# CPU_superviser.net
KiCad netlist of a schematic drawn in Altium Designer
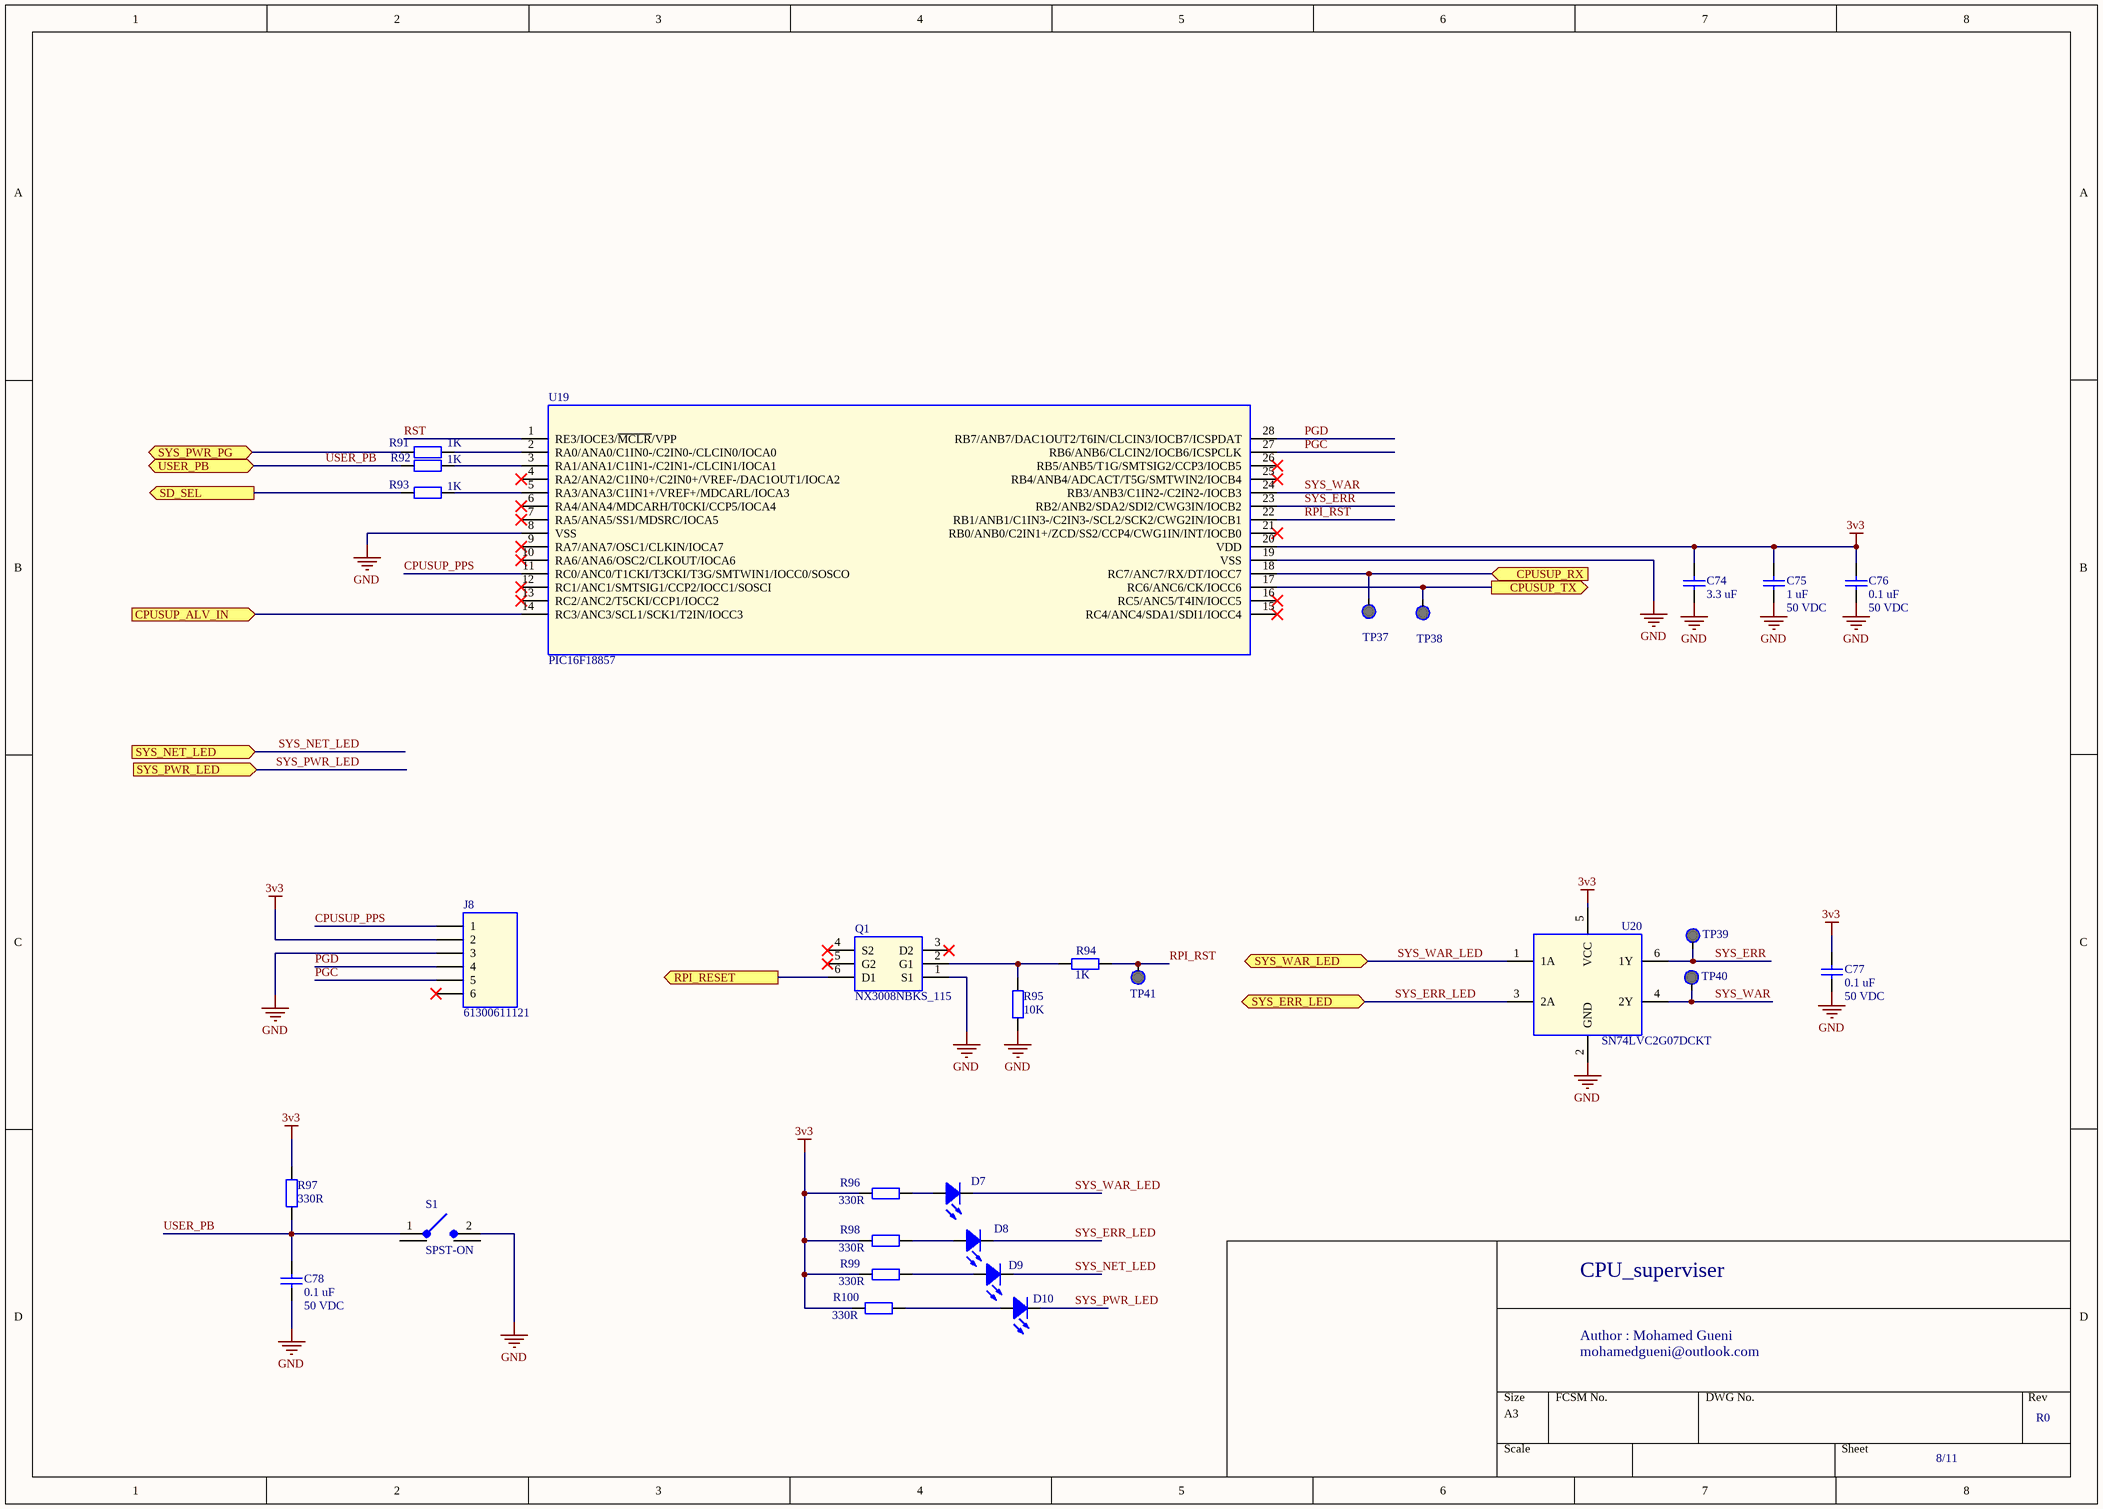
[diagram p0: CPU_superviser.SchDoc]

(export (version "E")
  (design (tool "Eeschema 10.0.6"))
  (components
    (comp (ref "C74")
      (value "Capacitor")
      (footprint "CAPC1608N")
      (fields (field (name "PART NUMBER") "CAP-000000008") (field (name "VALUE 1") "3.3 uF"))
      (libsource (lib "DB") (part "Capacitor"))
    )
    (comp (ref "C75")
      (value "Capacitor")
      (footprint "CAPC1608N")
      (fields
        (field (name "PART NUMBER") "CAP-000000005")
        (field (name "VALUE 1") "1 uF")
        (field (name "VALUE 2") "50 VDC")
      )
      (libsource (lib "DB") (part "Capacitor"))
    )
    (comp (ref "C76")
      (value "Capacitor")
      (footprint "CAPC1608N")
      (fields
        (field (name "PART NUMBER") "CAP-000000003")
        (field (name "VALUE 1") "0.1 uF")
        (field (name "VALUE 2") "50 VDC")
      )
      (libsource (lib "DB") (part "Capacitor"))
    )
    (comp (ref "C77")
      (value "Capacitor")
      (footprint "CAPC1608N")
      (fields
        (field (name "PART NUMBER") "CAP-000000003")
        (field (name "VALUE 1") "0.1 uF")
        (field (name "VALUE 2") "50 VDC")
      )
      (libsource (lib "DB") (part "Capacitor"))
    )
    (comp (ref "C78")
      (value "Capacitor")
      (footprint "CAPC1608N")
      (fields
        (field (name "PART NUMBER") "CAP-000000003")
        (field (name "VALUE 1") "0.1 uF")
        (field (name "VALUE 2") "50 VDC")
      )
      (libsource (lib "DB") (part "Capacitor"))
    )
    (comp (ref "D7")
      (value "150060BS75000")
      (footprint "LED0603")
      (fields (field (name "PART NUMBER") "LED-000000003"))
      (libsource (lib "DB") (part "LED"))
    )
    (comp (ref "D8")
      (value "150060RS75000")
      (footprint "LED0603")
      (fields (field (name "PART NUMBER") "LED-000000001"))
      (libsource (lib "DB") (part "LED"))
    )
    (comp (ref "D9")
      (value "150060GS75000")
      (footprint "LED0603")
      (fields (field (name "PART NUMBER") "LED-000000002"))
      (libsource (lib "DB") (part "LED"))
    )
    (comp (ref "D10")
      (value "150060GS75000")
      (footprint "LED0603")
      (fields (field (name "PART NUMBER") "LED-000000002"))
      (libsource (lib "DB") (part "LED"))
    )
    (comp (ref "J8")
      (value "61300611121")
      (footprint "HDRV6W64P0X254")
      (fields (field (name "PART NUMBER") "CON-000000010"))
      (libsource (lib "DB") (part "61300611121"))
    )
    (comp (ref "Q1")
      (value "NX3008NBKS_115")
      (footprint "SOT65P210X110-6N")
      (fields (field (name "PART NUMBER") "TRM-000000002"))
      (libsource (lib "DB") (part "NX3008NBKS_115"))
    )
    (comp (ref "R91")
      (value "Resistor")
      (footprint "RESC1608N")
      (fields (field (name "PART NUMBER") "RES-000000001") (field (name "VALUE 1") "1K"))
      (libsource (lib "DB") (part "Resistor"))
    )
    (comp (ref "R92")
      (value "Resistor")
      (footprint "RESC1608N")
      (fields (field (name "PART NUMBER") "RES-000000001") (field (name "VALUE 1") "1K"))
      (libsource (lib "DB") (part "Resistor"))
    )
    (comp (ref "R93")
      (value "Resistor")
      (footprint "RESC1608N")
      (fields (field (name "PART NUMBER") "RES-000000001") (field (name "VALUE 1") "1K"))
      (libsource (lib "DB") (part "Resistor"))
    )
    (comp (ref "R94")
      (value "Resistor")
      (footprint "RESC1608N")
      (fields (field (name "PART NUMBER") "RES-000000001") (field (name "VALUE 1") "1K"))
      (libsource (lib "DB") (part "Resistor"))
    )
    (comp (ref "R95")
      (value "Resistor")
      (footprint "RESC1608N")
      (fields (field (name "PART NUMBER") "RES-000000007") (field (name "VALUE 1") "10K"))
      (libsource (lib "") (part "Resistor_1"))
    )
    (comp (ref "R96")
      (value "Resistor")
      (footprint "RESC1608N")
      (fields (field (name "PART NUMBER") "RES-000000008") (field (name "VALUE 1") "330R"))
      (libsource (lib "DB") (part "Resistor"))
    )
    (comp (ref "R97")
      (value "Resistor")
      (footprint "RESC1608N")
      (fields (field (name "PART NUMBER") "RES-000000008") (field (name "VALUE 1") "330R"))
      (libsource (lib "") (part "Resistor_1"))
    )
    (comp (ref "R98")
      (value "Resistor")
      (footprint "RESC1608N")
      (fields (field (name "PART NUMBER") "RES-000000008") (field (name "VALUE 1") "330R"))
      (libsource (lib "DB") (part "Resistor"))
    )
    (comp (ref "R99")
      (value "Resistor")
      (footprint "RESC1608N")
      (fields (field (name "PART NUMBER") "RES-000000008") (field (name "VALUE 1") "330R"))
      (libsource (lib "DB") (part "Resistor"))
    )
    (comp (ref "R100")
      (value "Resistor")
      (footprint "RESC1608N")
      (fields (field (name "PART NUMBER") "RES-000000008") (field (name "VALUE 1") "330R"))
      (libsource (lib "DB") (part "Resistor"))
    )
    (comp (ref "S1")
      (value "SPST-ON")
      (footprint "118250272")
      (fields (field (name "PART NUMBER") "S-000000001"))
      (libsource (lib "DB") (part "SPST-ON"))
    )
    (comp (ref "TP37")
      (value "Test Point")
      (footprint "TP")
      (fields (field (name "PART NUMBER") "MIS-000000002"))
      (libsource (lib "DB") (part "TP"))
    )
    (comp (ref "TP38")
      (value "Test Point")
      (footprint "TP")
      (fields (field (name "PART NUMBER") "MIS-000000002"))
      (libsource (lib "DB") (part "TP"))
    )
    (comp (ref "TP39")
      (value "Test Point")
      (footprint "TP")
      (fields (field (name "PART NUMBER") "MIS-000000002"))
      (libsource (lib "DB") (part "TP"))
    )
    (comp (ref "TP40")
      (value "Test Point")
      (footprint "TP")
      (fields (field (name "PART NUMBER") "MIS-000000002"))
      (libsource (lib "DB") (part "TP"))
    )
    (comp (ref "TP41")
      (value "Test Point")
      (footprint "TP")
      (fields (field (name "PART NUMBER") "MIS-000000002"))
      (libsource (lib "DB") (part "TP"))
    )
    (comp (ref "U19")
      (value "PIC16F18857")
      (footprint "SOP65P780X200-28N")
      (fields (field (name "PART NUMBER") "MCU-000000002"))
      (libsource (lib "DB") (part "PIC16F18857"))
    )
    (comp (ref "U20")
      (value "SN74LVC2G07DCKT")
      (footprint "SOT65P210X1106N")
      (description "Dual Buffer/Driver with Open-Drain Output")
      (fields
        (field (name "MOUSER PART NUMBER") "595-SN74LVC2G07DCKT")
        (field (name "PART NUMBER") "GIC-000000009")
      )
      (libsource (lib "DB") (part "SN74LVC2G07DCKT"))
    )
  )
  (nets
    (net (code "1") (name "/CPUSUP_ALV_IN") (class "Default")
      (node (ref "U19") (pin "14") (pinfunction "RC3/ANC3/SCL1/SCK1/T2IN/IOCC3_14") (pintype "passive"))
    )
    (net (code "2") (name "/CPUSUP_PPS") (class "Default")
      (node (ref "J8") (pin "1") (pinfunction "1_1") (pintype "passive"))
      (node (ref "U19") (pin "11") (pinfunction "RC0/ANC0/T1CKI/T3CKI/T3G/SMTWIN1/IOCC0/SOSCO_11") (pintype "passive"))
    )
    (net (code "3") (name "/CPUSUP_RX") (class "Default")
      (node (ref "TP37") (pin "1") (pinfunction "1_1") (pintype "passive"))
      (node (ref "U19") (pin "18") (pinfunction "RC7/ANC7/RX/DT/IOCC7_18") (pintype "passive"))
    )
    (net (code "4") (name "/CPUSUP_TX") (class "Default")
      (node (ref "TP38") (pin "1") (pinfunction "1_1") (pintype "passive"))
      (node (ref "U19") (pin "17") (pinfunction "RC6/ANC6/CK/IOCC6_17") (pintype "passive"))
    )
    (net (code "5") (name "/PGC") (class "Default")
      (node (ref "J8") (pin "5") (pinfunction "5_5") (pintype "passive"))
      (node (ref "U19") (pin "27") (pinfunction "RB6/ANB6/CLCIN2/IOCB6/ICSPCLK_27") (pintype "passive"))
    )
    (net (code "6") (name "/PGD") (class "Default")
      (node (ref "J8") (pin "4") (pinfunction "4_4") (pintype "passive"))
      (node (ref "U19") (pin "28") (pinfunction "RB7/ANB7/DAC1OUT2/T6IN/CLCIN3/IOCB7/ICSPDAT_28") (pintype "passive"))
    )
    (net (code "7") (name "/RPI_RESET") (class "Default")
      (node (ref "Q1") (pin "6") (pinfunction "D1_6") (pintype "passive"))
    )
    (net (code "8") (name "/RPI_RST") (class "Default")
      (node (ref "R94") (pin "2") (pinfunction "2_2") (pintype "passive"))
      (node (ref "TP41") (pin "1") (pinfunction "1_1") (pintype "passive"))
      (node (ref "U19") (pin "22") (pinfunction "RB1/ANB1/C1IN3-/C2IN3-/SCL2/SCK2/CWG2IN/IOCB1_22") (pintype "passive"))
    )
    (net (code "9") (name "/RST") (class "Default")
      (node (ref "U19") (pin "1") (pinfunction "RE3/IOCE3/~{MCLR}/VPP_1") (pintype "passive"))
    )
    (net (code "10") (name "/SD_SEL") (class "Default")
      (node (ref "R93") (pin "1") (pinfunction "1_1") (pintype "passive"))
    )
    (net (code "11") (name "/SYS_ERR") (class "Default")
      (node (ref "TP39") (pin "1") (pinfunction "1_1") (pintype "passive"))
      (node (ref "U19") (pin "23") (pinfunction "RB2/ANB2/SDA2/SDI2/CWG3IN/IOCB2_23") (pintype "passive"))
      (node (ref "U20") (pin "6") (pinfunction "1Y_6") (pintype "passive"))
    )
    (net (code "12") (name "/SYS_ERR_LED") (class "Default")
      (node (ref "D8") (pin "1") (pinfunction "K_1") (pintype "passive"))
      (node (ref "U20") (pin "3") (pinfunction "2A_3") (pintype "passive"))
    )
    (net (code "13") (name "/SYS_NET_LED") (class "Default")
      (node (ref "D9") (pin "1") (pinfunction "K_1") (pintype "passive"))
    )
    (net (code "14") (name "/SYS_PWR_LED") (class "Default")
      (node (ref "D10") (pin "1") (pinfunction "K_1") (pintype "passive"))
    )
    (net (code "15") (name "/SYS_PWR_PG") (class "Default")
      (node (ref "R91") (pin "1") (pinfunction "1_1") (pintype "passive"))
    )
    (net (code "16") (name "/SYS_WAR") (class "Default")
      (node (ref "TP40") (pin "1") (pinfunction "1_1") (pintype "passive"))
      (node (ref "U19") (pin "24") (pinfunction "RB3/ANB3/C1IN2-/C2IN2-/IOCB3_24") (pintype "passive"))
      (node (ref "U20") (pin "4") (pinfunction "2Y_4") (pintype "passive"))
    )
    (net (code "17") (name "/SYS_WAR_LED") (class "Default")
      (node (ref "D7") (pin "1") (pinfunction "K_1") (pintype "passive"))
      (node (ref "U20") (pin "1") (pinfunction "1A_1") (pintype "passive"))
    )
    (net (code "18") (name "/USER_PB") (class "Default")
      (node (ref "C78") (pin "2") (pinfunction "2_2") (pintype "passive"))
      (node (ref "R92") (pin "1") (pinfunction "1_1") (pintype "passive"))
      (node (ref "R97") (pin "1") (pinfunction "1_1") (pintype "passive"))
      (node (ref "S1") (pin "1") (pinfunction "COM_1") (pintype "passive"))
    )
    (net (code "19") (name "3v3") (class "Default")
      (node (ref "C74") (pin "2") (pinfunction "2_2") (pintype "passive"))
      (node (ref "C75") (pin "2") (pinfunction "2_2") (pintype "passive"))
      (node (ref "C76") (pin "2") (pinfunction "2_2") (pintype "passive"))
      (node (ref "C77") (pin "2") (pinfunction "2_2") (pintype "passive"))
      (node (ref "J8") (pin "2") (pinfunction "2_2") (pintype "passive"))
      (node (ref "R100") (pin "1") (pinfunction "1_1") (pintype "passive"))
      (node (ref "R96") (pin "1") (pinfunction "1_1") (pintype "passive"))
      (node (ref "R97") (pin "2") (pinfunction "2_2") (pintype "passive"))
      (node (ref "R98") (pin "1") (pinfunction "1_1") (pintype "passive"))
      (node (ref "R99") (pin "1") (pinfunction "1_1") (pintype "passive"))
      (node (ref "U19") (pin "20") (pinfunction "VDD_20") (pintype "passive"))
      (node (ref "U20") (pin "5") (pinfunction "VCC_5") (pintype "passive"))
    )
    (net (code "20") (name "GND") (class "Default")
      (node (ref "C74") (pin "1") (pinfunction "1_1") (pintype "passive"))
      (node (ref "C75") (pin "1") (pinfunction "1_1") (pintype "passive"))
      (node (ref "C76") (pin "1") (pinfunction "1_1") (pintype "passive"))
      (node (ref "C77") (pin "1") (pinfunction "1_1") (pintype "passive"))
      (node (ref "C78") (pin "1") (pinfunction "1_1") (pintype "passive"))
      (node (ref "J8") (pin "3") (pinfunction "3_3") (pintype "passive"))
      (node (ref "Q1") (pin "1") (pinfunction "S1_1") (pintype "passive"))
      (node (ref "R95") (pin "1") (pinfunction "1_1") (pintype "passive"))
      (node (ref "S1") (pin "2") (pinfunction "NO_2") (pintype "passive"))
      (node (ref "U19") (pin "19") (pinfunction "VSS_19") (pintype "passive"))
      (node (ref "U19") (pin "8") (pinfunction "VSS_8") (pintype "passive"))
      (node (ref "U20") (pin "2") (pinfunction "GND_2") (pintype "passive"))
    )
    (net (code "21") (name "Net-(D7-A)") (class "Default")
      (node (ref "D7") (pin "2") (pinfunction "A_2") (pintype "passive"))
      (node (ref "R96") (pin "2") (pinfunction "2_2") (pintype "passive"))
    )
    (net (code "22") (name "Net-(D8-A)") (class "Default")
      (node (ref "D8") (pin "2") (pinfunction "A_2") (pintype "passive"))
      (node (ref "R98") (pin "2") (pinfunction "2_2") (pintype "passive"))
    )
    (net (code "23") (name "Net-(D9-A)") (class "Default")
      (node (ref "D9") (pin "2") (pinfunction "A_2") (pintype "passive"))
      (node (ref "R99") (pin "2") (pinfunction "2_2") (pintype "passive"))
    )
    (net (code "24") (name "Net-(D10-A)") (class "Default")
      (node (ref "D10") (pin "2") (pinfunction "A_2") (pintype "passive"))
      (node (ref "R100") (pin "2") (pinfunction "2_2") (pintype "passive"))
    )
    (net (code "25") (name "Net-(Q1-G1)") (class "Default")
      (node (ref "Q1") (pin "2") (pinfunction "G1_2") (pintype "passive"))
      (node (ref "R94") (pin "1") (pinfunction "1_1") (pintype "passive"))
      (node (ref "R95") (pin "2") (pinfunction "2_2") (pintype "passive"))
    )
    (net (code "26") (name "Net-(U19-RA0{slash}ANA0{slash}C1IN0-{slash}C2IN0-{slash}CLCIN0{slash}IOCA0)") (class "Default")
      (node (ref "R91") (pin "2") (pinfunction "2_2") (pintype "passive"))
      (node (ref "U19") (pin "2") (pinfunction "RA0/ANA0/C1IN0-/C2IN0-/CLCIN0/IOCA0_2") (pintype "passive"))
    )
    (net (code "27") (name "Net-(U19-RA1{slash}ANA1{slash}C1IN1-{slash}C2IN1-{slash}CLCIN1{slash}IOCA1)") (class "Default")
      (node (ref "R92") (pin "2") (pinfunction "2_2") (pintype "passive"))
      (node (ref "U19") (pin "3") (pinfunction "RA1/ANA1/C1IN1-/C2IN1-/CLCIN1/IOCA1_3") (pintype "passive"))
    )
    (net (code "28") (name "Net-(U19-RA3{slash}ANA3{slash}C1IN1+{slash}VREF+{slash}MDCARL{slash}IOCA3)") (class "Default")
      (node (ref "R93") (pin "2") (pinfunction "2_2") (pintype "passive"))
      (node (ref "U19") (pin "5") (pinfunction "RA3/ANA3/C1IN1+/VREF+/MDCARL/IOCA3_5") (pintype "passive"))
    )
    (net (code "29") (name "unconnected-(J8-Pad6)") (class "Default")
      (node (ref "J8") (pin "6") (pinfunction "6_6") (pintype "passive+no_connect"))
    )
    (net (code "30") (name "unconnected-(Q1-D2-Pad3)") (class "Default")
      (node (ref "Q1") (pin "3") (pinfunction "D2_3") (pintype "passive+no_connect"))
    )
    (net (code "31") (name "unconnected-(Q1-G2-Pad5)") (class "Default")
      (node (ref "Q1") (pin "5") (pinfunction "G2_5") (pintype "passive+no_connect"))
    )
    (net (code "32") (name "unconnected-(Q1-S2-Pad4)") (class "Default")
      (node (ref "Q1") (pin "4") (pinfunction "S2_4") (pintype "passive+no_connect"))
    )
    (net (code "33") (name "unconnected-(S1-PadMH1)") (class "Default")
      (node (ref "S1") (pin "MH1") (pinfunction "MH1_MH1") (pintype "passive"))
    )
    (net (code "34") (name "unconnected-(S1-PadMH2)") (class "Default")
      (node (ref "S1") (pin "MH2") (pinfunction "MH2_MH2") (pintype "passive"))
    )
    (net (code "35") (name "unconnected-(U19-RA2{slash}ANA2{slash}C1IN0+{slash}C2IN0+{slash}VREF-{slash}DAC1OUT1{slash}IOCA2-Pad4)") (class "Default")
      (node (ref "U19") (pin "4") (pinfunction "RA2/ANA2/C1IN0+/C2IN0+/VREF-/DAC1OUT1/IOCA2_4") (pintype "passive+no_connect"))
    )
    (net (code "36") (name "unconnected-(U19-RA4{slash}ANA4{slash}MDCARH{slash}T0CKI{slash}CCP5{slash}IOCA4-Pad6)") (class "Default")
      (node (ref "U19") (pin "6") (pinfunction "RA4/ANA4/MDCARH/T0CKI/CCP5/IOCA4_6") (pintype "passive+no_connect"))
    )
    (net (code "37") (name "unconnected-(U19-RA5{slash}ANA5{slash}SS1{slash}MDSRC{slash}IOCA5-Pad7)") (class "Default")
      (node (ref "U19") (pin "7") (pinfunction "RA5/ANA5/SS1/MDSRC/IOCA5_7") (pintype "passive+no_connect"))
    )
    (net (code "38") (name "unconnected-(U19-RA6{slash}ANA6{slash}OSC2{slash}CLKOUT{slash}IOCA6-Pad10)") (class "Default")
      (node (ref "U19") (pin "10") (pinfunction "RA6/ANA6/OSC2/CLKOUT/IOCA6_10") (pintype "passive+no_connect"))
    )
    (net (code "39") (name "unconnected-(U19-RA7{slash}ANA7{slash}OSC1{slash}CLKIN{slash}IOCA7-Pad9)") (class "Default")
      (node (ref "U19") (pin "9") (pinfunction "RA7/ANA7/OSC1/CLKIN/IOCA7_9") (pintype "passive+no_connect"))
    )
    (net (code "40") (name "unconnected-(U19-RB0{slash}ANB0{slash}C2IN1+{slash}ZCD{slash}SS2{slash}CCP4{slash}CWG1IN{slash}INT{slash}IOCB0-Pad21)") (class "Default")
      (node (ref "U19") (pin "21") (pinfunction "RB0/ANB0/C2IN1+/ZCD/SS2/CCP4/CWG1IN/INT/IOCB0_21") (pintype "passive+no_connect"))
    )
    (net (code "41") (name "unconnected-(U19-RB4{slash}ANB4{slash}ADCACT{slash}T5G{slash}SMTWIN2{slash}IOCB4-Pad25)") (class "Default")
      (node (ref "U19") (pin "25") (pinfunction "RB4/ANB4/ADCACT/T5G/SMTWIN2/IOCB4_25") (pintype "passive+no_connect"))
    )
    (net (code "42") (name "unconnected-(U19-RB5{slash}ANB5{slash}T1G{slash}SMTSIG2{slash}CCP3{slash}IOCB5-Pad26)") (class "Default")
      (node (ref "U19") (pin "26") (pinfunction "RB5/ANB5/T1G/SMTSIG2/CCP3/IOCB5_26") (pintype "passive+no_connect"))
    )
    (net (code "43") (name "unconnected-(U19-RC1{slash}ANC1{slash}SMTSIG1{slash}CCP2{slash}IOCC1{slash}SOSCI-Pad12)") (class "Default")
      (node (ref "U19") (pin "12") (pinfunction "RC1/ANC1/SMTSIG1/CCP2/IOCC1/SOSCI_12") (pintype "passive+no_connect"))
    )
    (net (code "44") (name "unconnected-(U19-RC2{slash}ANC2{slash}T5CKI{slash}CCP1{slash}IOCC2-Pad13)") (class "Default")
      (node (ref "U19") (pin "13") (pinfunction "RC2/ANC2/T5CKI/CCP1/IOCC2_13") (pintype "passive+no_connect"))
    )
    (net (code "45") (name "unconnected-(U19-RC4{slash}ANC4{slash}SDA1{slash}SDI1{slash}IOCC4-Pad15)") (class "Default")
      (node (ref "U19") (pin "15") (pinfunction "RC4/ANC4/SDA1/SDI1/IOCC4_15") (pintype "passive+no_connect"))
    )
    (net (code "46") (name "unconnected-(U19-RC5{slash}ANC5{slash}T4IN{slash}IOCC5-Pad16)") (class "Default")
      (node (ref "U19") (pin "16") (pinfunction "RC5/ANC5/T4IN/IOCC5_16") (pintype "passive+no_connect"))
    )
  )
)
